# infra_red.net
KiCad netlist of a schematic drawn in Altium Designer
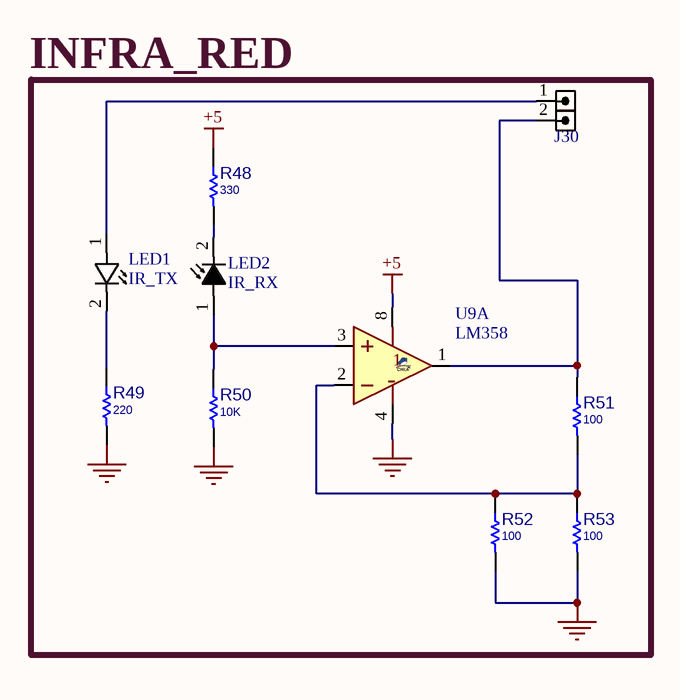
[diagram p0: infra_red.SchDoc]

(export (version "E")
  (design (tool "Eeschema 10.0.6"))
  (components
    (comp (ref "J30")
      (value "HDRM2")
      (footprint "HDR_M_1X2")
      (description "CONN, HEADER, Male, pitch: 2.54mm, 2POS")
      (libsource (lib "conn_header_2.54mm_st") (part "HDR_M_1X2"))
    )
    (comp (ref "LED1")
      (value "IR_TX")
      (footprint "LED5MM_RED")
      (description "CREATED BY J")
      (libsource (lib "AvrDevelopmentBoard") (part "IR_TX"))
    )
    (comp (ref "LED2")
      (value "IR_RX")
      (footprint "LED5MM_RED")
      (description "CREATED BY J")
      (libsource (lib "AvrDevelopmentBoard") (part "IR_RX"))
    )
    (comp (ref "R48")
      (value "330")
      (footprint "R025W_AX04")
      (description "RESISTOR, THD")
      (fields (field (name "MANF_P#") "RK73H1ETTP4701F") (field (name "MANF") "KOA SPEER"))
      (libsource (lib "passive_thd") (part "RES_THD"))
    )
    (comp (ref "R49")
      (value "220")
      (footprint "R025W_AX04")
      (description "RESISTOR, THD")
      (fields (field (name "MANF_P#") "RK73H1ETTP4701F") (field (name "MANF") "KOA SPEER"))
      (libsource (lib "passive_thd") (part "RES_THD"))
    )
    (comp (ref "R50")
      (value "10K")
      (footprint "R025W_AX04")
      (description "RESISTOR, THD")
      (fields (field (name "MANF_P#") "RK73H1ETTP4701F") (field (name "MANF") "KOA SPEER"))
      (libsource (lib "passive_thd") (part "RES_THD"))
    )
    (comp (ref "R51")
      (value "100")
      (footprint "R025W_AX04")
      (description "RESISTOR, THD")
      (fields (field (name "MANF_P#") "RK73H1ETTP4701F") (field (name "MANF") "KOA SPEER"))
      (libsource (lib "passive_thd") (part "RES_THD"))
    )
    (comp (ref "R52")
      (value "100")
      (footprint "R025W_AX04")
      (description "RESISTOR, THD")
      (fields (field (name "MANF_P#") "RK73H1ETTP4701F") (field (name "MANF") "KOA SPEER"))
      (libsource (lib "passive_thd") (part "RES_THD"))
    )
    (comp (ref "R53")
      (value "100")
      (footprint "R025W_AX04")
      (description "RESISTOR, THD")
      (fields (field (name "MANF_P#") "RK73H1ETTP4701F") (field (name "MANF") "KOA SPEER"))
      (libsource (lib "passive_thd") (part "RES_THD"))
    )
    (comp (ref "U9")
      (value "LM358")
      (footprint "DIP_8")
      (description "AMP, Dual, Low-Power")
      (fields (field (name "MANF") "Texas Instruments, Fairchild") (field (name "MANF_P#") "LM358AN"))
      (libsource (lib "AvrDevelopmentBoard") (part "LM358_DIP8"))
    )
  )
  (nets
    (net (code "1") (name "+5") (class "Default")
      (node (ref "R48") (pin "1") (pinfunction "1_1") (pintype "passive"))
      (node (ref "U9") (pin "8") (pinfunction "V+_8") (pintype "passive"))
    )
    (net (code "2") (name "GND") (class "Default")
      (node (ref "R49") (pin "2") (pinfunction "2_2") (pintype "passive"))
      (node (ref "R50") (pin "2") (pinfunction "2_2") (pintype "passive"))
      (node (ref "R52") (pin "2") (pinfunction "2_2") (pintype "passive"))
      (node (ref "R53") (pin "2") (pinfunction "2_2") (pintype "passive"))
      (node (ref "U9") (pin "4") (pinfunction "V-_4") (pintype "passive"))
    )
    (net (code "3") (name "Net-(LED1-ANODE)") (class "Default")
      (node (ref "J30") (pin "1") (pinfunction "1_1") (pintype "passive"))
      (node (ref "LED1") (pin "1") (pinfunction "ANODE_1") (pintype "passive"))
    )
    (net (code "4") (name "Net-(LED1-CATHODE)") (class "Default")
      (node (ref "LED1") (pin "2") (pinfunction "CATHODE_2") (pintype "passive"))
      (node (ref "R49") (pin "1") (pinfunction "1_1") (pintype "passive"))
    )
    (net (code "5") (name "Net-(LED2-ANODE)") (class "Default")
      (node (ref "LED2") (pin "1") (pinfunction "ANODE_1") (pintype "passive"))
      (node (ref "R50") (pin "1") (pinfunction "1_1") (pintype "passive"))
      (node (ref "U9") (pin "3") (pinfunction "IN+_3") (pintype "passive"))
    )
    (net (code "6") (name "Net-(LED2-CATHODE)") (class "Default")
      (node (ref "LED2") (pin "2") (pinfunction "CATHODE_2") (pintype "passive"))
      (node (ref "R48") (pin "2") (pinfunction "2_2") (pintype "passive"))
    )
    (net (code "7") (name "Net-(U9A-IN-)") (class "Default")
      (node (ref "R51") (pin "2") (pinfunction "2_2") (pintype "passive"))
      (node (ref "R52") (pin "1") (pinfunction "1_1") (pintype "passive"))
      (node (ref "R53") (pin "1") (pinfunction "1_1") (pintype "passive"))
      (node (ref "U9") (pin "2") (pinfunction "IN-_2") (pintype "passive"))
    )
    (net (code "8") (name "Net-(U9A-OUT)") (class "Default")
      (node (ref "J30") (pin "2") (pinfunction "2_2") (pintype "passive"))
      (node (ref "R51") (pin "1") (pinfunction "1_1") (pintype "passive"))
      (node (ref "U9") (pin "1") (pinfunction "OUT_1") (pintype "passive"))
    )
  )
)
